# schematic.net
KiCad netlist of a schematic drawn in EasyEDA
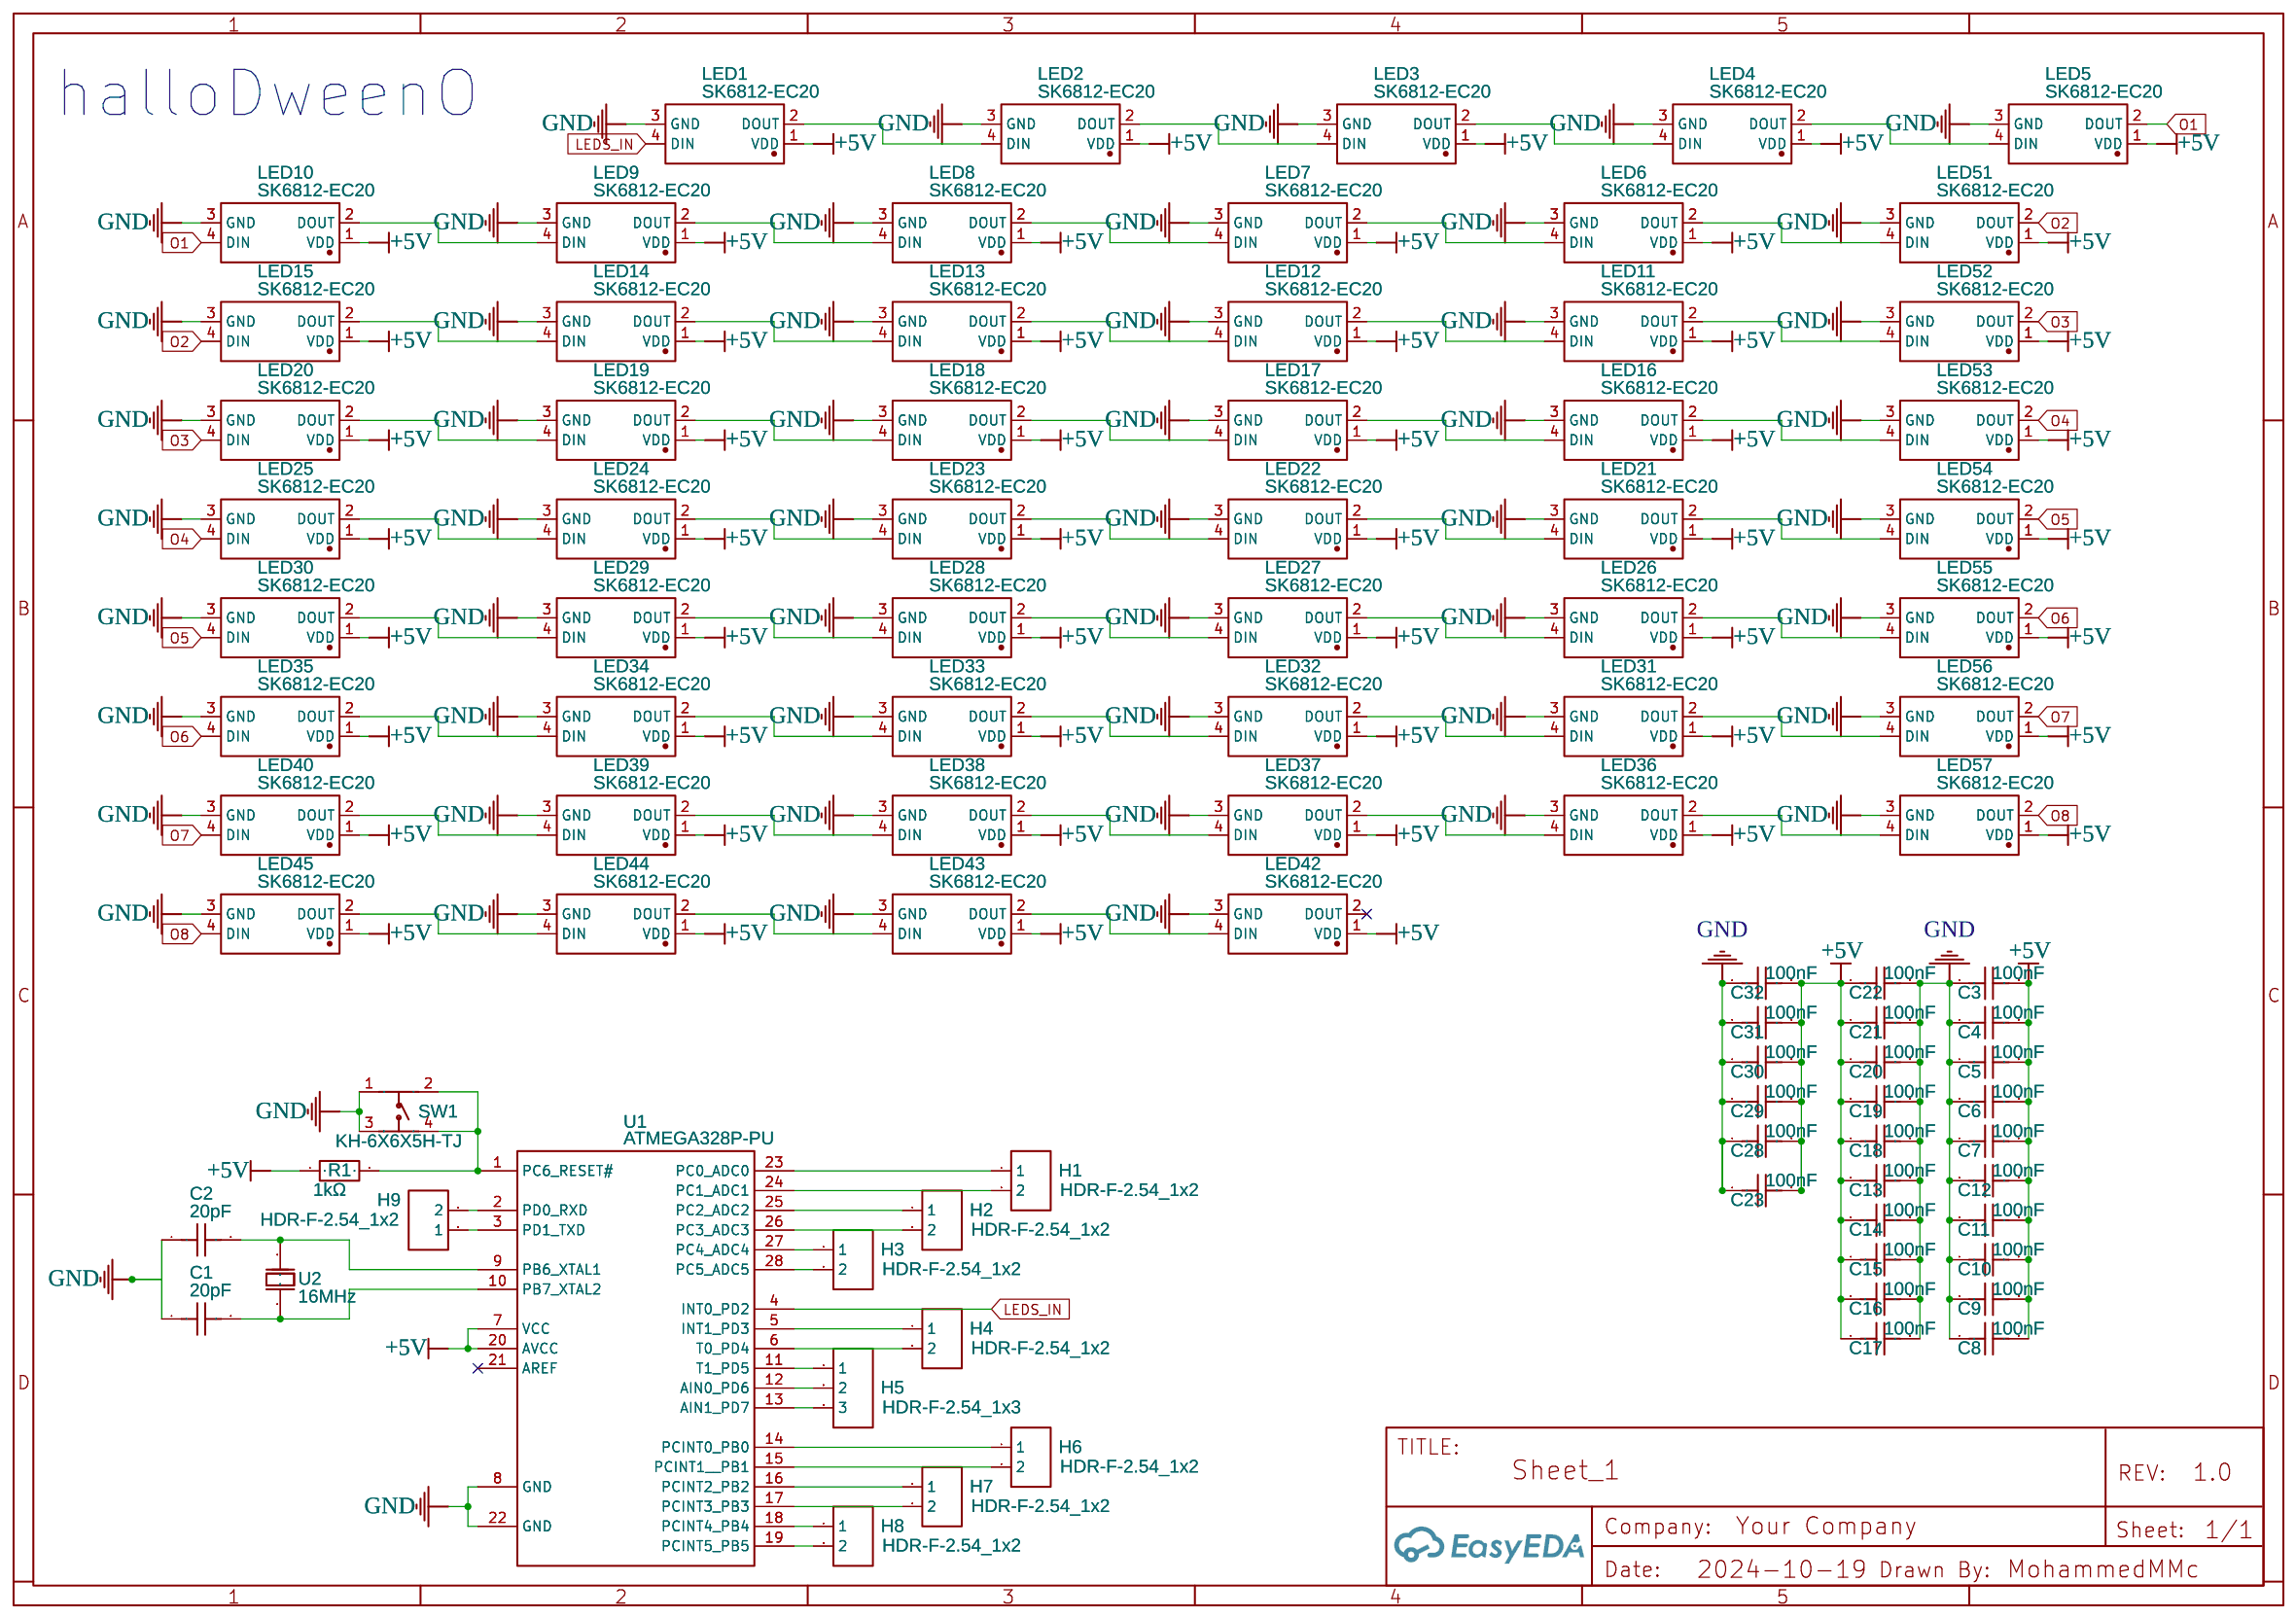
[diagram p0: schematic sheet]

(export (version "E")
  (design (tool "Eeschema 10.0.6"))
  (components
    (comp (ref "C1")
      (value "20pF")
      (fields
        (field (name "Manufacturer Part") "DCC200J20COHF6FJ5A0")
        (field (name "Manufacturer") "SHM(南方宏明)")
      )
      (libsource (lib "") (part "DCC200J20COHF6FJ5A0"))
    )
    (comp (ref "C2")
      (value "20pF")
      (fields
        (field (name "Manufacturer Part") "DCC200J20COHF6FJ5A0")
        (field (name "Manufacturer") "SHM(南方宏明)")
      )
      (libsource (lib "") (part "DCC200J20COHF6FJ5A0"))
    )
    (comp (ref "C3")
      (value "100nF")
      (fields
        (field (name "Manufacturer Part") "CC0603KRX7R9BB104")
        (field (name "Manufacturer") "YAGEO(国巨)")
      )
      (libsource (lib "") (part "CC0603KRX7R9BB104"))
    )
    (comp (ref "C4")
      (value "100nF")
      (fields
        (field (name "Manufacturer Part") "CC0603KRX7R9BB104")
        (field (name "Manufacturer") "YAGEO(国巨)")
      )
      (libsource (lib "") (part "CC0603KRX7R9BB104"))
    )
    (comp (ref "C5")
      (value "100nF")
      (fields
        (field (name "Manufacturer Part") "CC0603KRX7R9BB104")
        (field (name "Manufacturer") "YAGEO(国巨)")
      )
      (libsource (lib "") (part "CC0603KRX7R9BB104"))
    )
    (comp (ref "C6")
      (value "100nF")
      (fields
        (field (name "Manufacturer Part") "CC0603KRX7R9BB104")
        (field (name "Manufacturer") "YAGEO(国巨)")
      )
      (libsource (lib "") (part "CC0603KRX7R9BB104"))
    )
    (comp (ref "C7")
      (value "100nF")
      (fields
        (field (name "Manufacturer Part") "CC0603KRX7R9BB104")
        (field (name "Manufacturer") "YAGEO(国巨)")
      )
      (libsource (lib "") (part "CC0603KRX7R9BB104"))
    )
    (comp (ref "C8")
      (value "100nF")
      (fields
        (field (name "Manufacturer Part") "CC0603KRX7R9BB104")
        (field (name "Manufacturer") "YAGEO(国巨)")
      )
      (libsource (lib "") (part "CC0603KRX7R9BB104"))
    )
    (comp (ref "C9")
      (value "100nF")
      (fields
        (field (name "Manufacturer Part") "CC0603KRX7R9BB104")
        (field (name "Manufacturer") "YAGEO(国巨)")
      )
      (libsource (lib "") (part "CC0603KRX7R9BB104"))
    )
    (comp (ref "C10")
      (value "100nF")
      (fields
        (field (name "Manufacturer Part") "CC0603KRX7R9BB104")
        (field (name "Manufacturer") "YAGEO(国巨)")
      )
      (libsource (lib "") (part "CC0603KRX7R9BB104"))
    )
    (comp (ref "C11")
      (value "100nF")
      (fields
        (field (name "Manufacturer Part") "CC0603KRX7R9BB104")
        (field (name "Manufacturer") "YAGEO(国巨)")
      )
      (libsource (lib "") (part "CC0603KRX7R9BB104"))
    )
    (comp (ref "C12")
      (value "100nF")
      (fields
        (field (name "Manufacturer Part") "CC0603KRX7R9BB104")
        (field (name "Manufacturer") "YAGEO(国巨)")
      )
      (libsource (lib "") (part "CC0603KRX7R9BB104"))
    )
    (comp (ref "C13")
      (value "100nF")
      (fields
        (field (name "Manufacturer Part") "CC0603KRX7R9BB104")
        (field (name "Manufacturer") "YAGEO(国巨)")
      )
      (libsource (lib "") (part "CC0603KRX7R9BB104"))
    )
    (comp (ref "C14")
      (value "100nF")
      (fields
        (field (name "Manufacturer Part") "CC0603KRX7R9BB104")
        (field (name "Manufacturer") "YAGEO(国巨)")
      )
      (libsource (lib "") (part "CC0603KRX7R9BB104"))
    )
    (comp (ref "C15")
      (value "100nF")
      (fields
        (field (name "Manufacturer Part") "CC0603KRX7R9BB104")
        (field (name "Manufacturer") "YAGEO(国巨)")
      )
      (libsource (lib "") (part "CC0603KRX7R9BB104"))
    )
    (comp (ref "C16")
      (value "100nF")
      (fields
        (field (name "Manufacturer Part") "CC0603KRX7R9BB104")
        (field (name "Manufacturer") "YAGEO(国巨)")
      )
      (libsource (lib "") (part "CC0603KRX7R9BB104"))
    )
    (comp (ref "C17")
      (value "100nF")
      (fields
        (field (name "Manufacturer Part") "CC0603KRX7R9BB104")
        (field (name "Manufacturer") "YAGEO(国巨)")
      )
      (libsource (lib "") (part "CC0603KRX7R9BB104"))
    )
    (comp (ref "C18")
      (value "100nF")
      (fields
        (field (name "Manufacturer Part") "CC0603KRX7R9BB104")
        (field (name "Manufacturer") "YAGEO(国巨)")
      )
      (libsource (lib "") (part "CC0603KRX7R9BB104"))
    )
    (comp (ref "C19")
      (value "100nF")
      (fields
        (field (name "Manufacturer Part") "CC0603KRX7R9BB104")
        (field (name "Manufacturer") "YAGEO(国巨)")
      )
      (libsource (lib "") (part "CC0603KRX7R9BB104"))
    )
    (comp (ref "C20")
      (value "100nF")
      (fields
        (field (name "Manufacturer Part") "CC0603KRX7R9BB104")
        (field (name "Manufacturer") "YAGEO(国巨)")
      )
      (libsource (lib "") (part "CC0603KRX7R9BB104"))
    )
    (comp (ref "C21")
      (value "100nF")
      (fields
        (field (name "Manufacturer Part") "CC0603KRX7R9BB104")
        (field (name "Manufacturer") "YAGEO(国巨)")
      )
      (libsource (lib "") (part "CC0603KRX7R9BB104"))
    )
    (comp (ref "C22")
      (value "100nF")
      (fields
        (field (name "Manufacturer Part") "CC0603KRX7R9BB104")
        (field (name "Manufacturer") "YAGEO(国巨)")
      )
      (libsource (lib "") (part "CC0603KRX7R9BB104"))
    )
    (comp (ref "C23")
      (value "100nF")
      (fields
        (field (name "Manufacturer Part") "CC0603KRX7R9BB104")
        (field (name "Manufacturer") "YAGEO(国巨)")
      )
      (libsource (lib "") (part "CC0603KRX7R9BB104"))
    )
    (comp (ref "C28")
      (value "100nF")
      (fields
        (field (name "Manufacturer Part") "CC0603KRX7R9BB104")
        (field (name "Manufacturer") "YAGEO(国巨)")
      )
      (libsource (lib "") (part "CC0603KRX7R9BB104"))
    )
    (comp (ref "C29")
      (value "100nF")
      (fields
        (field (name "Manufacturer Part") "CC0603KRX7R9BB104")
        (field (name "Manufacturer") "YAGEO(国巨)")
      )
      (libsource (lib "") (part "CC0603KRX7R9BB104"))
    )
    (comp (ref "C30")
      (value "100nF")
      (fields
        (field (name "Manufacturer Part") "CC0603KRX7R9BB104")
        (field (name "Manufacturer") "YAGEO(国巨)")
      )
      (libsource (lib "") (part "CC0603KRX7R9BB104"))
    )
    (comp (ref "C31")
      (value "100nF")
      (fields
        (field (name "Manufacturer Part") "CC0603KRX7R9BB104")
        (field (name "Manufacturer") "YAGEO(国巨)")
      )
      (libsource (lib "") (part "CC0603KRX7R9BB104"))
    )
    (comp (ref "C32")
      (value "100nF")
      (fields
        (field (name "Manufacturer Part") "CC0603KRX7R9BB104")
        (field (name "Manufacturer") "YAGEO(国巨)")
      )
      (libsource (lib "") (part "CC0603KRX7R9BB104"))
    )
    (comp (ref "H1") (value "HDR-F-2.54_1x2") (libsource (lib "") (part "HDR-F-2.54_1x2")))
    (comp (ref "H2") (value "HDR-F-2.54_1x2") (libsource (lib "") (part "HDR-F-2.54_1x2")))
    (comp (ref "H3") (value "HDR-F-2.54_1x2") (libsource (lib "") (part "HDR-F-2.54_1x2")))
    (comp (ref "H4") (value "HDR-F-2.54_1x2") (libsource (lib "") (part "HDR-F-2.54_1x2")))
    (comp (ref "H5") (value "HDR-F-2.54_1x3") (libsource (lib "") (part "HDR-F-2.54_1x3")))
    (comp (ref "H6") (value "HDR-F-2.54_1x2") (libsource (lib "") (part "HDR-F-2.54_1x2")))
    (comp (ref "H7") (value "HDR-F-2.54_1x2") (libsource (lib "") (part "HDR-F-2.54_1x2")))
    (comp (ref "H8") (value "HDR-F-2.54_1x2") (libsource (lib "") (part "HDR-F-2.54_1x2")))
    (comp (ref "H9") (value "HDR-F-2.54_1x2") (libsource (lib "") (part "HDR-F-2.54_1x2_1")))
    (comp (ref "LED1")
      (value "SK6812-EC20")
      (fields (field (name "Manufacturer") "欧思科光电"))
      (libsource (lib "") (part "SK6812-EC20"))
    )
    (comp (ref "LED2")
      (value "SK6812-EC20")
      (fields (field (name "Manufacturer") "欧思科光电"))
      (libsource (lib "") (part "SK6812-EC20"))
    )
    (comp (ref "LED3")
      (value "SK6812-EC20")
      (fields (field (name "Manufacturer") "欧思科光电"))
      (libsource (lib "") (part "SK6812-EC20"))
    )
    (comp (ref "LED4")
      (value "SK6812-EC20")
      (fields (field (name "Manufacturer") "欧思科光电"))
      (libsource (lib "") (part "SK6812-EC20"))
    )
    (comp (ref "LED5")
      (value "SK6812-EC20")
      (fields (field (name "Manufacturer") "欧思科光电"))
      (libsource (lib "") (part "SK6812-EC20"))
    )
    (comp (ref "LED6")
      (value "SK6812-EC20")
      (fields (field (name "Manufacturer") "欧思科光电"))
      (libsource (lib "") (part "SK6812-EC20"))
    )
    (comp (ref "LED7")
      (value "SK6812-EC20")
      (fields (field (name "Manufacturer") "欧思科光电"))
      (libsource (lib "") (part "SK6812-EC20"))
    )
    (comp (ref "LED8")
      (value "SK6812-EC20")
      (fields (field (name "Manufacturer") "欧思科光电"))
      (libsource (lib "") (part "SK6812-EC20"))
    )
    (comp (ref "LED9")
      (value "SK6812-EC20")
      (fields (field (name "Manufacturer") "欧思科光电"))
      (libsource (lib "") (part "SK6812-EC20"))
    )
    (comp (ref "LED10")
      (value "SK6812-EC20")
      (fields (field (name "Manufacturer") "欧思科光电"))
      (libsource (lib "") (part "SK6812-EC20"))
    )
    (comp (ref "LED11")
      (value "SK6812-EC20")
      (fields (field (name "Manufacturer") "欧思科光电"))
      (libsource (lib "") (part "SK6812-EC20"))
    )
    (comp (ref "LED12")
      (value "SK6812-EC20")
      (fields (field (name "Manufacturer") "欧思科光电"))
      (libsource (lib "") (part "SK6812-EC20"))
    )
    (comp (ref "LED13")
      (value "SK6812-EC20")
      (fields (field (name "Manufacturer") "欧思科光电"))
      (libsource (lib "") (part "SK6812-EC20"))
    )
    (comp (ref "LED14")
      (value "SK6812-EC20")
      (fields (field (name "Manufacturer") "欧思科光电"))
      (libsource (lib "") (part "SK6812-EC20"))
    )
    (comp (ref "LED15")
      (value "SK6812-EC20")
      (fields (field (name "Manufacturer") "欧思科光电"))
      (libsource (lib "") (part "SK6812-EC20"))
    )
    (comp (ref "LED16")
      (value "SK6812-EC20")
      (fields (field (name "Manufacturer") "欧思科光电"))
      (libsource (lib "") (part "SK6812-EC20"))
    )
    (comp (ref "LED17")
      (value "SK6812-EC20")
      (fields (field (name "Manufacturer") "欧思科光电"))
      (libsource (lib "") (part "SK6812-EC20"))
    )
    (comp (ref "LED18")
      (value "SK6812-EC20")
      (fields (field (name "Manufacturer") "欧思科光电"))
      (libsource (lib "") (part "SK6812-EC20"))
    )
    (comp (ref "LED19")
      (value "SK6812-EC20")
      (fields (field (name "Manufacturer") "欧思科光电"))
      (libsource (lib "") (part "SK6812-EC20"))
    )
    (comp (ref "LED20")
      (value "SK6812-EC20")
      (fields (field (name "Manufacturer") "欧思科光电"))
      (libsource (lib "") (part "SK6812-EC20"))
    )
    (comp (ref "LED21")
      (value "SK6812-EC20")
      (fields (field (name "Manufacturer") "欧思科光电"))
      (libsource (lib "") (part "SK6812-EC20"))
    )
    (comp (ref "LED22")
      (value "SK6812-EC20")
      (fields (field (name "Manufacturer") "欧思科光电"))
      (libsource (lib "") (part "SK6812-EC20"))
    )
    (comp (ref "LED23")
      (value "SK6812-EC20")
      (fields (field (name "Manufacturer") "欧思科光电"))
      (libsource (lib "") (part "SK6812-EC20"))
    )
    (comp (ref "LED24")
      (value "SK6812-EC20")
      (fields (field (name "Manufacturer") "欧思科光电"))
      (libsource (lib "") (part "SK6812-EC20"))
    )
    (comp (ref "LED25")
      (value "SK6812-EC20")
      (fields (field (name "Manufacturer") "欧思科光电"))
      (libsource (lib "") (part "SK6812-EC20"))
    )
    (comp (ref "LED26")
      (value "SK6812-EC20")
      (fields (field (name "Manufacturer") "欧思科光电"))
      (libsource (lib "") (part "SK6812-EC20"))
    )
    (comp (ref "LED27")
      (value "SK6812-EC20")
      (fields (field (name "Manufacturer") "欧思科光电"))
      (libsource (lib "") (part "SK6812-EC20"))
    )
    (comp (ref "LED28")
      (value "SK6812-EC20")
      (fields (field (name "Manufacturer") "欧思科光电"))
      (libsource (lib "") (part "SK6812-EC20"))
    )
    (comp (ref "LED29")
      (value "SK6812-EC20")
      (fields (field (name "Manufacturer") "欧思科光电"))
      (libsource (lib "") (part "SK6812-EC20"))
    )
    (comp (ref "LED30")
      (value "SK6812-EC20")
      (fields (field (name "Manufacturer") "欧思科光电"))
      (libsource (lib "") (part "SK6812-EC20"))
    )
    (comp (ref "LED31")
      (value "SK6812-EC20")
      (fields (field (name "Manufacturer") "欧思科光电"))
      (libsource (lib "") (part "SK6812-EC20"))
    )
    (comp (ref "LED32")
      (value "SK6812-EC20")
      (fields (field (name "Manufacturer") "欧思科光电"))
      (libsource (lib "") (part "SK6812-EC20"))
    )
    (comp (ref "LED33")
      (value "SK6812-EC20")
      (fields (field (name "Manufacturer") "欧思科光电"))
      (libsource (lib "") (part "SK6812-EC20"))
    )
    (comp (ref "LED34")
      (value "SK6812-EC20")
      (fields (field (name "Manufacturer") "欧思科光电"))
      (libsource (lib "") (part "SK6812-EC20"))
    )
    (comp (ref "LED35")
      (value "SK6812-EC20")
      (fields (field (name "Manufacturer") "欧思科光电"))
      (libsource (lib "") (part "SK6812-EC20"))
    )
    (comp (ref "LED36")
      (value "SK6812-EC20")
      (fields (field (name "Manufacturer") "欧思科光电"))
      (libsource (lib "") (part "SK6812-EC20"))
    )
    (comp (ref "LED37")
      (value "SK6812-EC20")
      (fields (field (name "Manufacturer") "欧思科光电"))
      (libsource (lib "") (part "SK6812-EC20"))
    )
    (comp (ref "LED38")
      (value "SK6812-EC20")
      (fields (field (name "Manufacturer") "欧思科光电"))
      (libsource (lib "") (part "SK6812-EC20"))
    )
    (comp (ref "LED39")
      (value "SK6812-EC20")
      (fields (field (name "Manufacturer") "欧思科光电"))
      (libsource (lib "") (part "SK6812-EC20"))
    )
    (comp (ref "LED40")
      (value "SK6812-EC20")
      (fields (field (name "Manufacturer") "欧思科光电"))
      (libsource (lib "") (part "SK6812-EC20"))
    )
    (comp (ref "LED42")
      (value "SK6812-EC20")
      (fields (field (name "Manufacturer") "欧思科光电"))
      (libsource (lib "") (part "SK6812-EC20"))
    )
    (comp (ref "LED43")
      (value "SK6812-EC20")
      (fields (field (name "Manufacturer") "欧思科光电"))
      (libsource (lib "") (part "SK6812-EC20"))
    )
    (comp (ref "LED44")
      (value "SK6812-EC20")
      (fields (field (name "Manufacturer") "欧思科光电"))
      (libsource (lib "") (part "SK6812-EC20"))
    )
    (comp (ref "LED45")
      (value "SK6812-EC20")
      (fields (field (name "Manufacturer") "欧思科光电"))
      (libsource (lib "") (part "SK6812-EC20"))
    )
    (comp (ref "LED51")
      (value "SK6812-EC20")
      (fields (field (name "Manufacturer") "欧思科光电"))
      (libsource (lib "") (part "SK6812-EC20"))
    )
    (comp (ref "LED52")
      (value "SK6812-EC20")
      (fields (field (name "Manufacturer") "欧思科光电"))
      (libsource (lib "") (part "SK6812-EC20"))
    )
    (comp (ref "LED53")
      (value "SK6812-EC20")
      (fields (field (name "Manufacturer") "欧思科光电"))
      (libsource (lib "") (part "SK6812-EC20"))
    )
    (comp (ref "LED54")
      (value "SK6812-EC20")
      (fields (field (name "Manufacturer") "欧思科光电"))
      (libsource (lib "") (part "SK6812-EC20"))
    )
    (comp (ref "LED55")
      (value "SK6812-EC20")
      (fields (field (name "Manufacturer") "欧思科光电"))
      (libsource (lib "") (part "SK6812-EC20"))
    )
    (comp (ref "LED56")
      (value "SK6812-EC20")
      (fields (field (name "Manufacturer") "欧思科光电"))
      (libsource (lib "") (part "SK6812-EC20"))
    )
    (comp (ref "LED57")
      (value "SK6812-EC20")
      (fields (field (name "Manufacturer") "欧思科光电"))
      (libsource (lib "") (part "SK6812-EC20"))
    )
    (comp (ref "R1")
      (value "1kΩ")
      (fields (field (name "Manufacturer Part") "MF1/4W-1KΩ±1%T52") (field (name "Manufacturer") "华星机电"))
      (libsource (lib "") (part "MF1/4W-1KΩ±1%T52"))
    )
    (comp (ref "SW1")
      (value "KH-6X6X5H-TJ")
      (fields (field (name "Manufacturer") "kinghelm(金航标)"))
      (libsource (lib "") (part "KH-6X6X5H-TJ"))
    )
    (comp (ref "U1")
      (value "ATMEGA328P-PU")
      (fields (field (name "Manufacturer") "MICROCHIP(美国微芯)"))
      (libsource (lib "") (part "ATMEGA328P-PU"))
    )
    (comp (ref "U2")
      (value "16MHz")
      (fields (field (name "Manufacturer Part") "H1OSC-SUG-16M") (field (name "Manufacturer") "YXC(扬兴晶振)"))
      (libsource (lib "") (part "H1OSC-SUG-16M"))
    )
  )
  (nets
    (net (code "1") (name "+5V") (class "Default")
      (node (ref "C10") (pin "2") (pinfunction "2_2") (pintype "unspecified"))
      (node (ref "C11") (pin "2") (pinfunction "2_2") (pintype "unspecified"))
      (node (ref "C12") (pin "2") (pinfunction "2_2") (pintype "unspecified"))
      (node (ref "C13") (pin "1") (pinfunction "1_1") (pintype "unspecified"))
      (node (ref "C14") (pin "1") (pinfunction "1_1") (pintype "unspecified"))
      (node (ref "C15") (pin "1") (pinfunction "1_1") (pintype "unspecified"))
      (node (ref "C16") (pin "1") (pinfunction "1_1") (pintype "unspecified"))
      (node (ref "C17") (pin "1") (pinfunction "1_1") (pintype "unspecified"))
      (node (ref "C18") (pin "1") (pinfunction "1_1") (pintype "unspecified"))
      (node (ref "C19") (pin "1") (pinfunction "1_1") (pintype "unspecified"))
      (node (ref "C20") (pin "1") (pinfunction "1_1") (pintype "unspecified"))
      (node (ref "C21") (pin "1") (pinfunction "1_1") (pintype "unspecified"))
      (node (ref "C22") (pin "1") (pinfunction "1_1") (pintype "unspecified"))
      (node (ref "C23") (pin "2") (pinfunction "2_2") (pintype "unspecified"))
      (node (ref "C28") (pin "2") (pinfunction "2_2") (pintype "unspecified"))
      (node (ref "C29") (pin "2") (pinfunction "2_2") (pintype "unspecified"))
      (node (ref "C3") (pin "2") (pinfunction "2_2") (pintype "unspecified"))
      (node (ref "C30") (pin "2") (pinfunction "2_2") (pintype "unspecified"))
      (node (ref "C31") (pin "2") (pinfunction "2_2") (pintype "unspecified"))
      (node (ref "C32") (pin "2") (pinfunction "2_2") (pintype "unspecified"))
      (node (ref "C4") (pin "2") (pinfunction "2_2") (pintype "unspecified"))
      (node (ref "C5") (pin "2") (pinfunction "2_2") (pintype "unspecified"))
      (node (ref "C6") (pin "2") (pinfunction "2_2") (pintype "unspecified"))
      (node (ref "C7") (pin "2") (pinfunction "2_2") (pintype "unspecified"))
      (node (ref "C8") (pin "2") (pinfunction "2_2") (pintype "unspecified"))
      (node (ref "C9") (pin "2") (pinfunction "2_2") (pintype "unspecified"))
      (node (ref "LED1") (pin "1") (pinfunction "VDD_1") (pintype "unspecified"))
      (node (ref "LED10") (pin "1") (pinfunction "VDD_1") (pintype "unspecified"))
      (node (ref "LED11") (pin "1") (pinfunction "VDD_1") (pintype "unspecified"))
      (node (ref "LED12") (pin "1") (pinfunction "VDD_1") (pintype "unspecified"))
      (node (ref "LED13") (pin "1") (pinfunction "VDD_1") (pintype "unspecified"))
      (node (ref "LED14") (pin "1") (pinfunction "VDD_1") (pintype "unspecified"))
      (node (ref "LED15") (pin "1") (pinfunction "VDD_1") (pintype "unspecified"))
      (node (ref "LED16") (pin "1") (pinfunction "VDD_1") (pintype "unspecified"))
      (node (ref "LED17") (pin "1") (pinfunction "VDD_1") (pintype "unspecified"))
      (node (ref "LED18") (pin "1") (pinfunction "VDD_1") (pintype "unspecified"))
      (node (ref "LED19") (pin "1") (pinfunction "VDD_1") (pintype "unspecified"))
      (node (ref "LED2") (pin "1") (pinfunction "VDD_1") (pintype "unspecified"))
      (node (ref "LED20") (pin "1") (pinfunction "VDD_1") (pintype "unspecified"))
      (node (ref "LED21") (pin "1") (pinfunction "VDD_1") (pintype "unspecified"))
      (node (ref "LED22") (pin "1") (pinfunction "VDD_1") (pintype "unspecified"))
      (node (ref "LED23") (pin "1") (pinfunction "VDD_1") (pintype "unspecified"))
      (node (ref "LED24") (pin "1") (pinfunction "VDD_1") (pintype "unspecified"))
      (node (ref "LED25") (pin "1") (pinfunction "VDD_1") (pintype "unspecified"))
      (node (ref "LED26") (pin "1") (pinfunction "VDD_1") (pintype "unspecified"))
      (node (ref "LED27") (pin "1") (pinfunction "VDD_1") (pintype "unspecified"))
      (node (ref "LED28") (pin "1") (pinfunction "VDD_1") (pintype "unspecified"))
      (node (ref "LED29") (pin "1") (pinfunction "VDD_1") (pintype "unspecified"))
      (node (ref "LED3") (pin "1") (pinfunction "VDD_1") (pintype "unspecified"))
      (node (ref "LED30") (pin "1") (pinfunction "VDD_1") (pintype "unspecified"))
      (node (ref "LED31") (pin "1") (pinfunction "VDD_1") (pintype "unspecified"))
      (node (ref "LED32") (pin "1") (pinfunction "VDD_1") (pintype "unspecified"))
      (node (ref "LED33") (pin "1") (pinfunction "VDD_1") (pintype "unspecified"))
      (node (ref "LED34") (pin "1") (pinfunction "VDD_1") (pintype "unspecified"))
      (node (ref "LED35") (pin "1") (pinfunction "VDD_1") (pintype "unspecified"))
      (node (ref "LED36") (pin "1") (pinfunction "VDD_1") (pintype "unspecified"))
      (node (ref "LED37") (pin "1") (pinfunction "VDD_1") (pintype "unspecified"))
      (node (ref "LED38") (pin "1") (pinfunction "VDD_1") (pintype "unspecified"))
      (node (ref "LED39") (pin "1") (pinfunction "VDD_1") (pintype "unspecified"))
      (node (ref "LED4") (pin "1") (pinfunction "VDD_1") (pintype "unspecified"))
      (node (ref "LED40") (pin "1") (pinfunction "VDD_1") (pintype "unspecified"))
      (node (ref "LED42") (pin "1") (pinfunction "VDD_1") (pintype "unspecified"))
      (node (ref "LED43") (pin "1") (pinfunction "VDD_1") (pintype "unspecified"))
      (node (ref "LED44") (pin "1") (pinfunction "VDD_1") (pintype "unspecified"))
      (node (ref "LED45") (pin "1") (pinfunction "VDD_1") (pintype "unspecified"))
      (node (ref "LED5") (pin "1") (pinfunction "VDD_1") (pintype "unspecified"))
      (node (ref "LED51") (pin "1") (pinfunction "VDD_1") (pintype "unspecified"))
      (node (ref "LED52") (pin "1") (pinfunction "VDD_1") (pintype "unspecified"))
      (node (ref "LED53") (pin "1") (pinfunction "VDD_1") (pintype "unspecified"))
      (node (ref "LED54") (pin "1") (pinfunction "VDD_1") (pintype "unspecified"))
      (node (ref "LED55") (pin "1") (pinfunction "VDD_1") (pintype "unspecified"))
      (node (ref "LED56") (pin "1") (pinfunction "VDD_1") (pintype "unspecified"))
      (node (ref "LED57") (pin "1") (pinfunction "VDD_1") (pintype "unspecified"))
      (node (ref "LED6") (pin "1") (pinfunction "VDD_1") (pintype "unspecified"))
      (node (ref "LED7") (pin "1") (pinfunction "VDD_1") (pintype "unspecified"))
      (node (ref "LED8") (pin "1") (pinfunction "VDD_1") (pintype "unspecified"))
      (node (ref "LED9") (pin "1") (pinfunction "VDD_1") (pintype "unspecified"))
      (node (ref "R1") (pin "1") (pinfunction "1_1") (pintype "unspecified"))
      (node (ref "U1") (pin "20") (pinfunction "AVCC_20") (pintype "passive"))
      (node (ref "U1") (pin "7") (pinfunction "VCC_7") (pintype "passive"))
    )
    (net (code "2") (name "GND") (class "Default")
      (node (ref "C1") (pin "1") (pinfunction "1_1") (pintype "unspecified"))
      (node (ref "C10") (pin "1") (pinfunction "1_1") (pintype "unspecified"))
      (node (ref "C11") (pin "1") (pinfunction "1_1") (pintype "unspecified"))
      (node (ref "C12") (pin "1") (pinfunction "1_1") (pintype "unspecified"))
      (node (ref "C13") (pin "2") (pinfunction "2_2") (pintype "unspecified"))
      (node (ref "C14") (pin "2") (pinfunction "2_2") (pintype "unspecified"))
      (node (ref "C15") (pin "2") (pinfunction "2_2") (pintype "unspecified"))
      (node (ref "C16") (pin "2") (pinfunction "2_2") (pintype "unspecified"))
      (node (ref "C17") (pin "2") (pinfunction "2_2") (pintype "unspecified"))
      (node (ref "C18") (pin "2") (pinfunction "2_2") (pintype "unspecified"))
      (node (ref "C19") (pin "2") (pinfunction "2_2") (pintype "unspecified"))
      (node (ref "C2") (pin "1") (pinfunction "1_1") (pintype "unspecified"))
      (node (ref "C20") (pin "2") (pinfunction "2_2") (pintype "unspecified"))
      (node (ref "C21") (pin "2") (pinfunction "2_2") (pintype "unspecified"))
      (node (ref "C22") (pin "2") (pinfunction "2_2") (pintype "unspecified"))
      (node (ref "C23") (pin "1") (pinfunction "1_1") (pintype "unspecified"))
      (node (ref "C28") (pin "1") (pinfunction "1_1") (pintype "unspecified"))
      (node (ref "C29") (pin "1") (pinfunction "1_1") (pintype "unspecified"))
      (node (ref "C3") (pin "1") (pinfunction "1_1") (pintype "unspecified"))
      (node (ref "C30") (pin "1") (pinfunction "1_1") (pintype "unspecified"))
      (node (ref "C31") (pin "1") (pinfunction "1_1") (pintype "unspecified"))
      (node (ref "C32") (pin "1") (pinfunction "1_1") (pintype "unspecified"))
      (node (ref "C4") (pin "1") (pinfunction "1_1") (pintype "unspecified"))
      (node (ref "C5") (pin "1") (pinfunction "1_1") (pintype "unspecified"))
      (node (ref "C6") (pin "1") (pinfunction "1_1") (pintype "unspecified"))
      (node (ref "C7") (pin "1") (pinfunction "1_1") (pintype "unspecified"))
      (node (ref "C8") (pin "1") (pinfunction "1_1") (pintype "unspecified"))
      (node (ref "C9") (pin "1") (pinfunction "1_1") (pintype "unspecified"))
      (node (ref "LED1") (pin "3") (pinfunction "GND_3") (pintype "unspecified"))
      (node (ref "LED10") (pin "3") (pinfunction "GND_3") (pintype "unspecified"))
      (node (ref "LED11") (pin "3") (pinfunction "GND_3") (pintype "unspecified"))
      (node (ref "LED12") (pin "3") (pinfunction "GND_3") (pintype "unspecified"))
      (node (ref "LED13") (pin "3") (pinfunction "GND_3") (pintype "unspecified"))
      (node (ref "LED14") (pin "3") (pinfunction "GND_3") (pintype "unspecified"))
      (node (ref "LED15") (pin "3") (pinfunction "GND_3") (pintype "unspecified"))
      (node (ref "LED16") (pin "3") (pinfunction "GND_3") (pintype "unspecified"))
      (node (ref "LED17") (pin "3") (pinfunction "GND_3") (pintype "unspecified"))
      (node (ref "LED18") (pin "3") (pinfunction "GND_3") (pintype "unspecified"))
      (node (ref "LED19") (pin "3") (pinfunction "GND_3") (pintype "unspecified"))
      (node (ref "LED2") (pin "3") (pinfunction "GND_3") (pintype "unspecified"))
      (node (ref "LED20") (pin "3") (pinfunction "GND_3") (pintype "unspecified"))
      (node (ref "LED21") (pin "3") (pinfunction "GND_3") (pintype "unspecified"))
      (node (ref "LED22") (pin "3") (pinfunction "GND_3") (pintype "unspecified"))
      (node (ref "LED23") (pin "3") (pinfunction "GND_3") (pintype "unspecified"))
      (node (ref "LED24") (pin "3") (pinfunction "GND_3") (pintype "unspecified"))
      (node (ref "LED25") (pin "3") (pinfunction "GND_3") (pintype "unspecified"))
      (node (ref "LED26") (pin "3") (pinfunction "GND_3") (pintype "unspecified"))
      (node (ref "LED27") (pin "3") (pinfunction "GND_3") (pintype "unspecified"))
      (node (ref "LED28") (pin "3") (pinfunction "GND_3") (pintype "unspecified"))
      (node (ref "LED29") (pin "3") (pinfunction "GND_3") (pintype "unspecified"))
      (node (ref "LED3") (pin "3") (pinfunction "GND_3") (pintype "unspecified"))
      (node (ref "LED30") (pin "3") (pinfunction "GND_3") (pintype "unspecified"))
      (node (ref "LED31") (pin "3") (pinfunction "GND_3") (pintype "unspecified"))
      (node (ref "LED32") (pin "3") (pinfunction "GND_3") (pintype "unspecified"))
      (node (ref "LED33") (pin "3") (pinfunction "GND_3") (pintype "unspecified"))
      (node (ref "LED34") (pin "3") (pinfunction "GND_3") (pintype "unspecified"))
      (node (ref "LED35") (pin "3") (pinfunction "GND_3") (pintype "unspecified"))
      (node (ref "LED36") (pin "3") (pinfunction "GND_3") (pintype "unspecified"))
      (node (ref "LED37") (pin "3") (pinfunction "GND_3") (pintype "unspecified"))
      (node (ref "LED38") (pin "3") (pinfunction "GND_3") (pintype "unspecified"))
      (node (ref "LED39") (pin "3") (pinfunction "GND_3") (pintype "unspecified"))
      (node (ref "LED4") (pin "3") (pinfunction "GND_3") (pintype "unspecified"))
      (node (ref "LED40") (pin "3") (pinfunction "GND_3") (pintype "unspecified"))
      (node (ref "LED42") (pin "3") (pinfunction "GND_3") (pintype "unspecified"))
      (node (ref "LED43") (pin "3") (pinfunction "GND_3") (pintype "unspecified"))
      (node (ref "LED44") (pin "3") (pinfunction "GND_3") (pintype "unspecified"))
      (node (ref "LED45") (pin "3") (pinfunction "GND_3") (pintype "unspecified"))
      (node (ref "LED5") (pin "3") (pinfunction "GND_3") (pintype "unspecified"))
      (node (ref "LED51") (pin "3") (pinfunction "GND_3") (pintype "unspecified"))
      (node (ref "LED52") (pin "3") (pinfunction "GND_3") (pintype "unspecified"))
      (node (ref "LED53") (pin "3") (pinfunction "GND_3") (pintype "unspecified"))
      (node (ref "LED54") (pin "3") (pinfunction "GND_3") (pintype "unspecified"))
      (node (ref "LED55") (pin "3") (pinfunction "GND_3") (pintype "unspecified"))
      (node (ref "LED56") (pin "3") (pinfunction "GND_3") (pintype "unspecified"))
      (node (ref "LED57") (pin "3") (pinfunction "GND_3") (pintype "unspecified"))
      (node (ref "LED6") (pin "3") (pinfunction "GND_3") (pintype "unspecified"))
      (node (ref "LED7") (pin "3") (pinfunction "GND_3") (pintype "unspecified"))
      (node (ref "LED8") (pin "3") (pinfunction "GND_3") (pintype "unspecified"))
      (node (ref "LED9") (pin "3") (pinfunction "GND_3") (pintype "unspecified"))
      (node (ref "SW1") (pin "1") (pinfunction "1_1") (pintype "unspecified"))
      (node (ref "SW1") (pin "3") (pinfunction "3_3") (pintype "unspecified"))
      (node (ref "U1") (pin "22") (pinfunction "GND_22") (pintype "passive"))
      (node (ref "U1") (pin "8") (pinfunction "GND_8") (pintype "passive"))
    )
    (net (code "3") (name "LEDS_IN") (class "Default")
      (node (ref "LED1") (pin "4") (pinfunction "DIN_4") (pintype "unspecified"))
      (node (ref "U1") (pin "4") (pinfunction "INT0_PD2_4") (pintype "bidirectional"))
    )
    (net (code "4") (name "Net-(LED1-DOUT)") (class "Default")
      (node (ref "LED1") (pin "2") (pinfunction "DOUT_2") (pintype "unspecified"))
      (node (ref "LED2") (pin "4") (pinfunction "DIN_4") (pintype "unspecified"))
    )
    (net (code "5") (name "Net-(LED2-DOUT)") (class "Default")
      (node (ref "LED2") (pin "2") (pinfunction "DOUT_2") (pintype "unspecified"))
      (node (ref "LED3") (pin "4") (pinfunction "DIN_4") (pintype "unspecified"))
    )
    (net (code "6") (name "Net-(LED3-DOUT)") (class "Default")
      (node (ref "LED3") (pin "2") (pinfunction "DOUT_2") (pintype "unspecified"))
      (node (ref "LED4") (pin "4") (pinfunction "DIN_4") (pintype "unspecified"))
    )
    (net (code "7") (name "Net-(LED4-DOUT)") (class "Default")
      (node (ref "LED4") (pin "2") (pinfunction "DOUT_2") (pintype "unspecified"))
      (node (ref "LED5") (pin "4") (pinfunction "DIN_4") (pintype "unspecified"))
    )
    (net (code "8") (name "Net-(LED6-DIN)") (class "Default")
      (node (ref "LED6") (pin "4") (pinfunction "DIN_4") (pintype "unspecified"))
      (node (ref "LED7") (pin "2") (pinfunction "DOUT_2") (pintype "unspecified"))
    )
    (net (code "9") (name "Net-(LED7-DIN)") (class "Default")
      (node (ref "LED7") (pin "4") (pinfunction "DIN_4") (pintype "unspecified"))
      (node (ref "LED8") (pin "2") (pinfunction "DOUT_2") (pintype "unspecified"))
    )
    (net (code "10") (name "Net-(LED8-DIN)") (class "Default")
      (node (ref "LED8") (pin "4") (pinfunction "DIN_4") (pintype "unspecified"))
      (node (ref "LED9") (pin "2") (pinfunction "DOUT_2") (pintype "unspecified"))
    )
    (net (code "11") (name "Net-(LED10-DOUT)") (class "Default")
      (node (ref "LED10") (pin "2") (pinfunction "DOUT_2") (pintype "unspecified"))
      (node (ref "LED9") (pin "4") (pinfunction "DIN_4") (pintype "unspecified"))
    )
    (net (code "12") (name "Net-(LED11-DIN)") (class "Default")
      (node (ref "LED11") (pin "4") (pinfunction "DIN_4") (pintype "unspecified"))
      (node (ref "LED12") (pin "2") (pinfunction "DOUT_2") (pintype "unspecified"))
    )
    (net (code "13") (name "Net-(LED11-DOUT)") (class "Default")
      (node (ref "LED11") (pin "2") (pinfunction "DOUT_2") (pintype "unspecified"))
      (node (ref "LED52") (pin "4") (pinfunction "DIN_4") (pintype "unspecified"))
    )
    (net (code "14") (name "Net-(LED12-DIN)") (class "Default")
      (node (ref "LED12") (pin "4") (pinfunction "DIN_4") (pintype "unspecified"))
      (node (ref "LED13") (pin "2") (pinfunction "DOUT_2") (pintype "unspecified"))
    )
    (net (code "15") (name "Net-(LED13-DIN)") (class "Default")
      (node (ref "LED13") (pin "4") (pinfunction "DIN_4") (pintype "unspecified"))
      (node (ref "LED14") (pin "2") (pinfunction "DOUT_2") (pintype "unspecified"))
    )
    (net (code "16") (name "Net-(LED14-DIN)") (class "Default")
      (node (ref "LED14") (pin "4") (pinfunction "DIN_4") (pintype "unspecified"))
      (node (ref "LED15") (pin "2") (pinfunction "DOUT_2") (pintype "unspecified"))
    )
    (net (code "17") (name "Net-(LED16-DIN)") (class "Default")
      (node (ref "LED16") (pin "4") (pinfunction "DIN_4") (pintype "unspecified"))
      (node (ref "LED17") (pin "2") (pinfunction "DOUT_2") (pintype "unspecified"))
    )
    (net (code "18") (name "Net-(LED16-DOUT)") (class "Default")
      (node (ref "LED16") (pin "2") (pinfunction "DOUT_2") (pintype "unspecified"))
      (node (ref "LED53") (pin "4") (pinfunction "DIN_4") (pintype "unspecified"))
    )
    (net (code "19") (name "Net-(LED17-DIN)") (class "Default")
      (node (ref "LED17") (pin "4") (pinfunction "DIN_4") (pintype "unspecified"))
      (node (ref "LED18") (pin "2") (pinfunction "DOUT_2") (pintype "unspecified"))
    )
    (net (code "20") (name "Net-(LED18-DIN)") (class "Default")
      (node (ref "LED18") (pin "4") (pinfunction "DIN_4") (pintype "unspecified"))
      (node (ref "LED19") (pin "2") (pinfunction "DOUT_2") (pintype "unspecified"))
    )
    (net (code "21") (name "Net-(LED19-DIN)") (class "Default")
      (node (ref "LED19") (pin "4") (pinfunction "DIN_4") (pintype "unspecified"))
      (node (ref "LED20") (pin "2") (pinfunction "DOUT_2") (pintype "unspecified"))
    )
    (net (code "22") (name "Net-(LED21-DIN)") (class "Default")
      (node (ref "LED21") (pin "4") (pinfunction "DIN_4") (pintype "unspecified"))
      (node (ref "LED22") (pin "2") (pinfunction "DOUT_2") (pintype "unspecified"))
    )
    (net (code "23") (name "Net-(LED21-DOUT)") (class "Default")
      (node (ref "LED21") (pin "2") (pinfunction "DOUT_2") (pintype "unspecified"))
      (node (ref "LED54") (pin "4") (pinfunction "DIN_4") (pintype "unspecified"))
    )
    (net (code "24") (name "Net-(LED22-DIN)") (class "Default")
      (node (ref "LED22") (pin "4") (pinfunction "DIN_4") (pintype "unspecified"))
      (node (ref "LED23") (pin "2") (pinfunction "DOUT_2") (pintype "unspecified"))
    )
    (net (code "25") (name "Net-(LED23-DIN)") (class "Default")
      (node (ref "LED23") (pin "4") (pinfunction "DIN_4") (pintype "unspecified"))
      (node (ref "LED24") (pin "2") (pinfunction "DOUT_2") (pintype "unspecified"))
    )
    (net (code "26") (name "Net-(LED24-DIN)") (class "Default")
      (node (ref "LED24") (pin "4") (pinfunction "DIN_4") (pintype "unspecified"))
      (node (ref "LED25") (pin "2") (pinfunction "DOUT_2") (pintype "unspecified"))
    )
    (net (code "27") (name "Net-(LED26-DIN)") (class "Default")
      (node (ref "LED26") (pin "4") (pinfunction "DIN_4") (pintype "unspecified"))
      (node (ref "LED27") (pin "2") (pinfunction "DOUT_2") (pintype "unspecified"))
    )
    (net (code "28") (name "Net-(LED26-DOUT)") (class "Default")
      (node (ref "LED26") (pin "2") (pinfunction "DOUT_2") (pintype "unspecified"))
      (node (ref "LED55") (pin "4") (pinfunction "DIN_4") (pintype "unspecified"))
    )
    (net (code "29") (name "Net-(LED27-DIN)") (class "Default")
      (node (ref "LED27") (pin "4") (pinfunction "DIN_4") (pintype "unspecified"))
      (node (ref "LED28") (pin "2") (pinfunction "DOUT_2") (pintype "unspecified"))
    )
    (net (code "30") (name "Net-(LED28-DIN)") (class "Default")
      (node (ref "LED28") (pin "4") (pinfunction "DIN_4") (pintype "unspecified"))
      (node (ref "LED29") (pin "2") (pinfunction "DOUT_2") (pintype "unspecified"))
    )
    (net (code "31") (name "Net-(LED29-DIN)") (class "Default")
      (node (ref "LED29") (pin "4") (pinfunction "DIN_4") (pintype "unspecified"))
      (node (ref "LED30") (pin "2") (pinfunction "DOUT_2") (pintype "unspecified"))
    )
    (net (code "32") (name "Net-(LED31-DIN)") (class "Default")
      (node (ref "LED31") (pin "4") (pinfunction "DIN_4") (pintype "unspecified"))
      (node (ref "LED32") (pin "2") (pinfunction "DOUT_2") (pintype "unspecified"))
    )
    (net (code "33") (name "Net-(LED31-DOUT)") (class "Default")
      (node (ref "LED31") (pin "2") (pinfunction "DOUT_2") (pintype "unspecified"))
      (node (ref "LED56") (pin "4") (pinfunction "DIN_4") (pintype "unspecified"))
    )
    (net (code "34") (name "Net-(LED32-DIN)") (class "Default")
      (node (ref "LED32") (pin "4") (pinfunction "DIN_4") (pintype "unspecified"))
      (node (ref "LED33") (pin "2") (pinfunction "DOUT_2") (pintype "unspecified"))
    )
    (net (code "35") (name "Net-(LED33-DIN)") (class "Default")
      (node (ref "LED33") (pin "4") (pinfunction "DIN_4") (pintype "unspecified"))
      (node (ref "LED34") (pin "2") (pinfunction "DOUT_2") (pintype "unspecified"))
    )
    (net (code "36") (name "Net-(LED34-DIN)") (class "Default")
      (node (ref "LED34") (pin "4") (pinfunction "DIN_4") (pintype "unspecified"))
      (node (ref "LED35") (pin "2") (pinfunction "DOUT_2") (pintype "unspecified"))
    )
    (net (code "37") (name "Net-(LED36-DIN)") (class "Default")
      (node (ref "LED36") (pin "4") (pinfunction "DIN_4") (pintype "unspecified"))
      (node (ref "LED37") (pin "2") (pinfunction "DOUT_2") (pintype "unspecified"))
    )
    (net (code "38") (name "Net-(LED36-DOUT)") (class "Default")
      (node (ref "LED36") (pin "2") (pinfunction "DOUT_2") (pintype "unspecified"))
      (node (ref "LED57") (pin "4") (pinfunction "DIN_4") (pintype "unspecified"))
    )
    (net (code "39") (name "Net-(LED37-DIN)") (class "Default")
      (node (ref "LED37") (pin "4") (pinfunction "DIN_4") (pintype "unspecified"))
      (node (ref "LED38") (pin "2") (pinfunction "DOUT_2") (pintype "unspecified"))
    )
    (net (code "40") (name "Net-(LED38-DIN)") (class "Default")
      (node (ref "LED38") (pin "4") (pinfunction "DIN_4") (pintype "unspecified"))
      (node (ref "LED39") (pin "2") (pinfunction "DOUT_2") (pintype "unspecified"))
    )
    (net (code "41") (name "Net-(LED39-DIN)") (class "Default")
      (node (ref "LED39") (pin "4") (pinfunction "DIN_4") (pintype "unspecified"))
      (node (ref "LED40") (pin "2") (pinfunction "DOUT_2") (pintype "unspecified"))
    )
    (net (code "42") (name "Net-(LED42-DIN)") (class "Default")
      (node (ref "LED42") (pin "4") (pinfunction "DIN_4") (pintype "unspecified"))
      (node (ref "LED43") (pin "2") (pinfunction "DOUT_2") (pintype "unspecified"))
    )
    (net (code "43") (name "Net-(LED43-DIN)") (class "Default")
      (node (ref "LED43") (pin "4") (pinfunction "DIN_4") (pintype "unspecified"))
      (node (ref "LED44") (pin "2") (pinfunction "DOUT_2") (pintype "unspecified"))
    )
    (net (code "44") (name "Net-(LED44-DIN)") (class "Default")
      (node (ref "LED44") (pin "4") (pinfunction "DIN_4") (pintype "unspecified"))
      (node (ref "LED45") (pin "2") (pinfunction "DOUT_2") (pintype "unspecified"))
    )
    (net (code "45") (name "Net-(LED51-DIN)") (class "Default")
      (node (ref "LED51") (pin "4") (pinfunction "DIN_4") (pintype "unspecified"))
      (node (ref "LED6") (pin "2") (pinfunction "DOUT_2") (pintype "unspecified"))
    )
    (net (code "46") (name "Net-(U1-AIN0_PD6)") (class "Default")
      (node (ref "H5") (pin "2") (pinfunction "2_2") (pintype "input"))
      (node (ref "U1") (pin "12") (pinfunction "AIN0_PD6_12") (pintype "bidirectional"))
    )
    (net (code "47") (name "Net-(U1-AIN1_PD7)") (class "Default")
      (node (ref "H5") (pin "3") (pinfunction "3_3") (pintype "input"))
      (node (ref "U1") (pin "13") (pinfunction "AIN1_PD7_13") (pintype "bidirectional"))
    )
    (net (code "48") (name "Net-(U1-INT1_PD3)") (class "Default")
      (node (ref "H4") (pin "1") (pinfunction "1_1") (pintype "input"))
      (node (ref "U1") (pin "5") (pinfunction "INT1_PD3_5") (pintype "bidirectional"))
    )
    (net (code "49") (name "Net-(U1-PB6_XTAL1)") (class "Default")
      (node (ref "C2") (pin "2") (pinfunction "2_2") (pintype "unspecified"))
      (node (ref "U1") (pin "9") (pinfunction "PB6_XTAL1_9") (pintype "bidirectional"))
      (node (ref "U2") (pin "2") (pinfunction "OSC2_2") (pintype "input"))
    )
    (net (code "50") (name "Net-(U1-PB7_XTAL2)") (class "Default")
      (node (ref "C1") (pin "2") (pinfunction "2_2") (pintype "unspecified"))
      (node (ref "U1") (pin "10") (pinfunction "PB7_XTAL2_10") (pintype "bidirectional"))
      (node (ref "U2") (pin "1") (pinfunction "OSC1_1") (pintype "input"))
    )
    (net (code "51") (name "Net-(U1-PC0_ADC0)") (class "Default")
      (node (ref "H1") (pin "1") (pinfunction "1_1") (pintype "input"))
      (node (ref "U1") (pin "23") (pinfunction "PC0_ADC0_23") (pintype "bidirectional"))
    )
    (net (code "52") (name "Net-(U1-PC1_ADC1)") (class "Default")
      (node (ref "H1") (pin "2") (pinfunction "2_2") (pintype "input"))
      (node (ref "U1") (pin "24") (pinfunction "PC1_ADC1_24") (pintype "bidirectional"))
    )
    (net (code "53") (name "Net-(U1-PC2_ADC2)") (class "Default")
      (node (ref "H2") (pin "1") (pinfunction "1_1") (pintype "input"))
      (node (ref "U1") (pin "25") (pinfunction "PC2_ADC2_25") (pintype "bidirectional"))
    )
    (net (code "54") (name "Net-(U1-PC3_ADC3)") (class "Default")
      (node (ref "H2") (pin "2") (pinfunction "2_2") (pintype "input"))
      (node (ref "U1") (pin "26") (pinfunction "PC3_ADC3_26") (pintype "bidirectional"))
    )
    (net (code "55") (name "Net-(U1-PC4_ADC4)") (class "Default")
      (node (ref "H3") (pin "1") (pinfunction "1_1") (pintype "input"))
      (node (ref "U1") (pin "27") (pinfunction "PC4_ADC4_27") (pintype "bidirectional"))
    )
    (net (code "56") (name "Net-(U1-PC5_ADC5)") (class "Default")
      (node (ref "H3") (pin "2") (pinfunction "2_2") (pintype "input"))
      (node (ref "U1") (pin "28") (pinfunction "PC5_ADC5_28") (pintype "bidirectional"))
    )
    (net (code "57") (name "Net-(U1-PC6_RESET#)") (class "Default")
      (node (ref "R1") (pin "2") (pinfunction "2_2") (pintype "unspecified"))
      (node (ref "SW1") (pin "2") (pinfunction "2_2") (pintype "unspecified"))
      (node (ref "SW1") (pin "4") (pinfunction "4_4") (pintype "unspecified"))
      (node (ref "U1") (pin "1") (pinfunction "PC6_RESET#_1") (pintype "bidirectional"))
    )
    (net (code "58") (name "Net-(U1-PCINT0_PB0)") (class "Default")
      (node (ref "H6") (pin "1") (pinfunction "1_1") (pintype "input"))
      (node (ref "U1") (pin "14") (pinfunction "PCINT0_PB0_14") (pintype "bidirectional"))
    )
    (net (code "59") (name "Net-(U1-PCINT1__PB1)") (class "Default")
      (node (ref "H6") (pin "2") (pinfunction "2_2") (pintype "input"))
      (node (ref "U1") (pin "15") (pinfunction "PCINT1__PB1_15") (pintype "bidirectional"))
    )
    (net (code "60") (name "Net-(U1-PCINT2_PB2)") (class "Default")
      (node (ref "H7") (pin "1") (pinfunction "1_1") (pintype "input"))
      (node (ref "U1") (pin "16") (pinfunction "PCINT2_PB2_16") (pintype "bidirectional"))
    )
    (net (code "61") (name "Net-(U1-PCINT3_PB3)") (class "Default")
      (node (ref "H7") (pin "2") (pinfunction "2_2") (pintype "input"))
      (node (ref "U1") (pin "17") (pinfunction "PCINT3_PB3_17") (pintype "bidirectional"))
    )
    (net (code "62") (name "Net-(U1-PCINT4_PB4)") (class "Default")
      (node (ref "H8") (pin "1") (pinfunction "1_1") (pintype "input"))
      (node (ref "U1") (pin "18") (pinfunction "PCINT4_PB4_18") (pintype "bidirectional"))
    )
    (net (code "63") (name "Net-(U1-PCINT5_PB5)") (class "Default")
      (node (ref "H8") (pin "2") (pinfunction "2_2") (pintype "input"))
      (node (ref "U1") (pin "19") (pinfunction "PCINT5_PB5_19") (pintype "bidirectional"))
    )
    (net (code "64") (name "Net-(U1-PD0_RXD)") (class "Default")
      (node (ref "H9") (pin "2") (pinfunction "2_2") (pintype "input"))
      (node (ref "U1") (pin "2") (pinfunction "PD0_RXD_2") (pintype "bidirectional"))
    )
    (net (code "65") (name "Net-(U1-PD1_TXD)") (class "Default")
      (node (ref "H9") (pin "1") (pinfunction "1_1") (pintype "input"))
      (node (ref "U1") (pin "3") (pinfunction "PD1_TXD_3") (pintype "bidirectional"))
    )
    (net (code "66") (name "Net-(U1-T0_PD4)") (class "Default")
      (node (ref "H4") (pin "2") (pinfunction "2_2") (pintype "input"))
      (node (ref "U1") (pin "6") (pinfunction "T0_PD4_6") (pintype "bidirectional"))
    )
    (net (code "67") (name "Net-(U1-T1_PD5)") (class "Default")
      (node (ref "H5") (pin "1") (pinfunction "1_1") (pintype "input"))
      (node (ref "U1") (pin "11") (pinfunction "T1_PD5_11") (pintype "bidirectional"))
    )
    (net (code "68") (name "O1") (class "Default")
      (node (ref "LED10") (pin "4") (pinfunction "DIN_4") (pintype "unspecified"))
      (node (ref "LED5") (pin "2") (pinfunction "DOUT_2") (pintype "unspecified"))
    )
    (net (code "69") (name "O2") (class "Default")
      (node (ref "LED15") (pin "4") (pinfunction "DIN_4") (pintype "unspecified"))
      (node (ref "LED51") (pin "2") (pinfunction "DOUT_2") (pintype "unspecified"))
    )
    (net (code "70") (name "O3") (class "Default")
      (node (ref "LED20") (pin "4") (pinfunction "DIN_4") (pintype "unspecified"))
      (node (ref "LED52") (pin "2") (pinfunction "DOUT_2") (pintype "unspecified"))
    )
    (net (code "71") (name "O4") (class "Default")
      (node (ref "LED25") (pin "4") (pinfunction "DIN_4") (pintype "unspecified"))
      (node (ref "LED53") (pin "2") (pinfunction "DOUT_2") (pintype "unspecified"))
    )
    (net (code "72") (name "O5") (class "Default")
      (node (ref "LED30") (pin "4") (pinfunction "DIN_4") (pintype "unspecified"))
      (node (ref "LED54") (pin "2") (pinfunction "DOUT_2") (pintype "unspecified"))
    )
    (net (code "73") (name "O6") (class "Default")
      (node (ref "LED35") (pin "4") (pinfunction "DIN_4") (pintype "unspecified"))
      (node (ref "LED55") (pin "2") (pinfunction "DOUT_2") (pintype "unspecified"))
    )
    (net (code "74") (name "O7") (class "Default")
      (node (ref "LED40") (pin "4") (pinfunction "DIN_4") (pintype "unspecified"))
      (node (ref "LED56") (pin "2") (pinfunction "DOUT_2") (pintype "unspecified"))
    )
    (net (code "75") (name "O8") (class "Default")
      (node (ref "LED45") (pin "4") (pinfunction "DIN_4") (pintype "unspecified"))
      (node (ref "LED57") (pin "2") (pinfunction "DOUT_2") (pintype "unspecified"))
    )
    (net (code "76") (name "unconnected-(LED42-DOUT-Pad2)") (class "Default")
      (node (ref "LED42") (pin "2") (pinfunction "DOUT_2") (pintype "unspecified+no_connect"))
    )
    (net (code "77") (name "unconnected-(U1-AREF-Pad21)") (class "Default")
      (node (ref "U1") (pin "21") (pinfunction "AREF_21") (pintype "passive+no_connect"))
    )
  )
)
